# ECUEXT1_23.net
KiCad netlist of a schematic drawn in Altium Designer
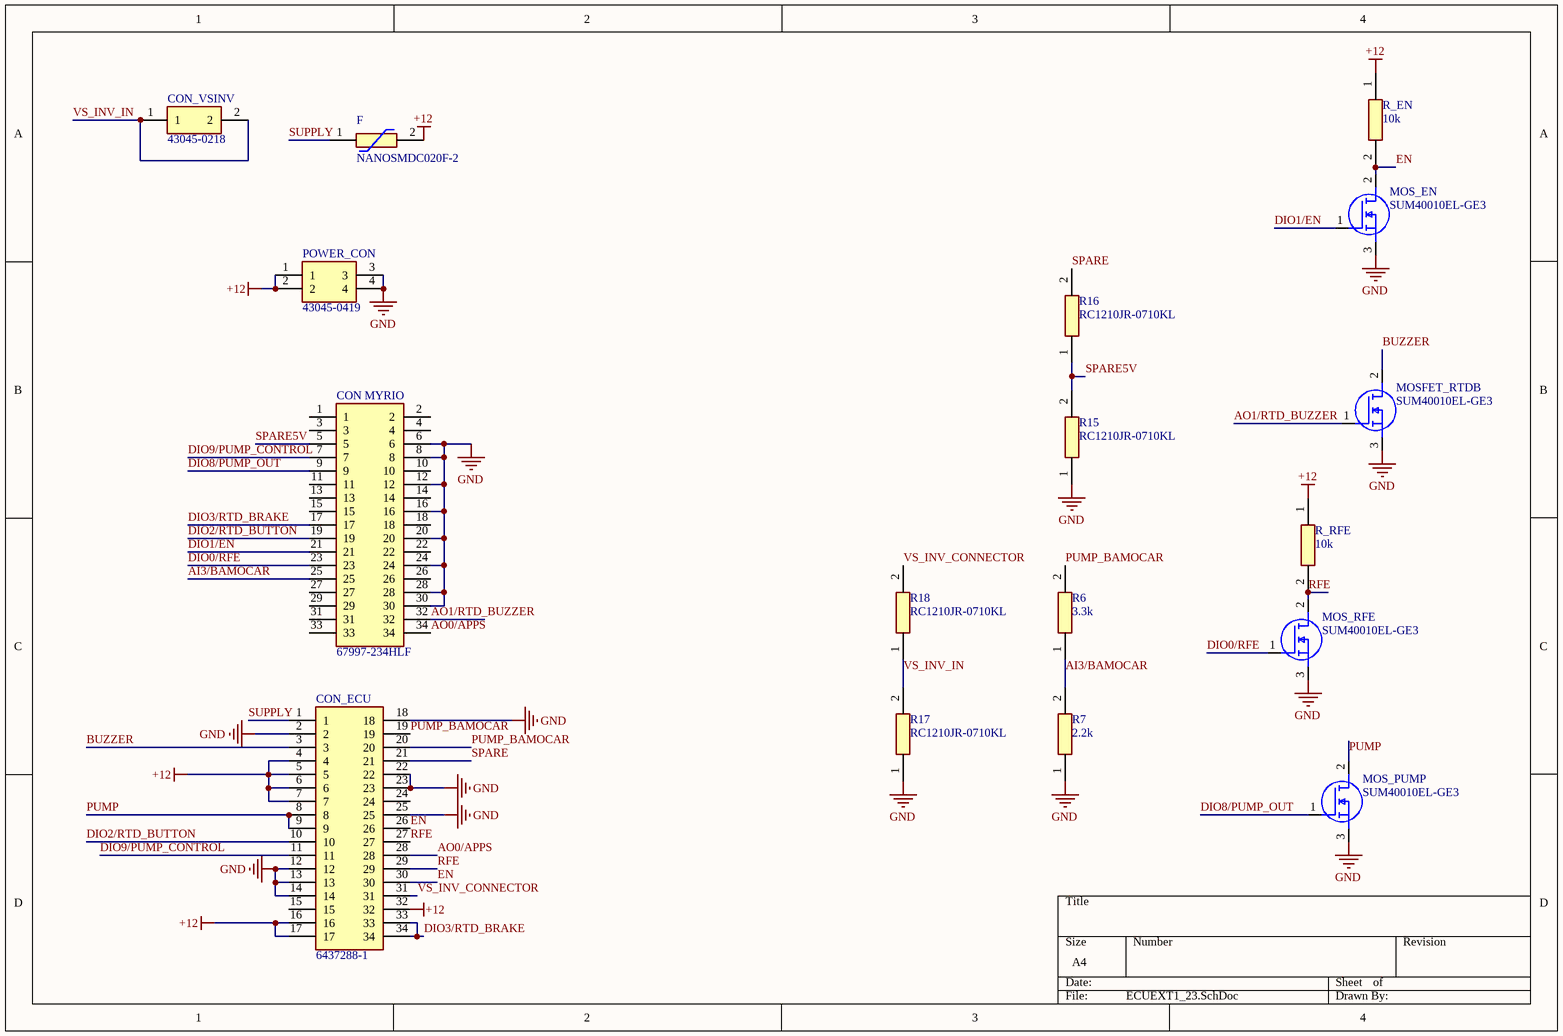
[diagram p0: ECUEXT1_23.SchDoc]

(export (version "E")
  (design (tool "Eeschema 10.0.6"))
  (components
    (comp (ref "CON MYRIO")
      (value "67997-234HLF")
      (footprint "SamacSys:HDRV34W67P254_2X17_4318X483X858P")
      (description "Connector")
      (fields (field (name "MOUSER PART NUMBER") "649-67997-234HLF"))
      (libsource (lib "*") (part "67997-234HLF"))
    )
    (comp (ref "CON_ECU")
      (value "6437288-1")
      (footprint "SamacSys:6437288-1")
      (description "Connector")
      (fields (field (name "MOUSER PART NUMBER") "571-6437288-1"))
      (libsource (lib "SamacSys") (part "6437288-1"))
    )
    (comp (ref "CON_VSINV")
      (value "43045-0218")
      (footprint "SamacSys:43045-02YY_181920")
      (description "Connector")
      (fields (field (name "MOUSER PART NUMBER") "538-43045-0218"))
      (libsource (lib "SamacSys") (part "43045-0218"))
    )
    (comp (ref "F")
      (value "NANOSMDC020F-2")
      (footprint "SamacSys:NANOSMDC016F2")
      (description "Resettable Fuse")
      (fields (field (name "MOUSER PART NUMBER") "650-NANOSMDC020F-2"))
      (libsource (lib "*") (part "NANOSMDC020F-2"))
    )
    (comp (ref "MOSFET_RTDB")
      (value "SUM40010EL-GE3")
      (footprint "SamacSys:SUM40010ELGE3")
      (description "MOSFET (N-Channel)")
      (fields (field (name "MOUSER PART NUMBER") "78-SUM40010EL-GE3"))
      (libsource (lib "SamacSys") (part "SUM40010EL-GE3"))
    )
    (comp (ref "MOS_EN")
      (value "SUM40010EL-GE3")
      (footprint "SamacSys:SUM40010ELGE3")
      (description "MOSFET (N-Channel)")
      (fields (field (name "MOUSER PART NUMBER") "78-SUM40010EL-GE3"))
      (libsource (lib "SamacSys") (part "SUM40010EL-GE3"))
    )
    (comp (ref "MOS_PUMP")
      (value "SUM40010EL-GE3")
      (footprint "SamacSys:SUM40010ELGE3")
      (description "MOSFET (N-Channel)")
      (fields (field (name "MOUSER PART NUMBER") "78-SUM40010EL-GE3"))
      (libsource (lib "SamacSys") (part "SUM40010EL-GE3"))
    )
    (comp (ref "MOS_RFE")
      (value "SUM40010EL-GE3")
      (footprint "SamacSys:SUM40010ELGE3")
      (description "MOSFET (N-Channel)")
      (fields (field (name "MOUSER PART NUMBER") "78-SUM40010EL-GE3"))
      (libsource (lib "SamacSys") (part "SUM40010EL-GE3"))
    )
    (comp (ref "POWER_CON")
      (value "43045-0419")
      (footprint "SamacSys:43045-04YY_181920")
      (description "Connector")
      (fields (field (name "MOUSER PART NUMBER") "538-43045-0419"))
      (libsource (lib "SamacSys") (part "43045-0419"))
    )
    (comp (ref "R6")
      (value "3.3k")
      (footprint "SamacSys:RESC3126X60N")
      (description "Resistor")
      (fields
        (field (name "MANUFACTURER_PART_NUMBER") "RC1210JR-0710KL")
        (field (name "MOUSER PART NUMBER") "603-RC1210JR-0710KL")
      )
      (libsource (lib "*") (part "RC1210JR-0710KL"))
    )
    (comp (ref "R7")
      (value "2.2k")
      (footprint "SamacSys:RESC3126X60N")
      (description "Resistor")
      (fields
        (field (name "MANUFACTURER_PART_NUMBER") "RC1210JR-0710KL")
        (field (name "MOUSER PART NUMBER") "603-RC1210JR-0710KL")
      )
      (libsource (lib "*") (part "RC1210JR-0710KL"))
    )
    (comp (ref "R15")
      (value "RC1210JR-0710KL")
      (footprint "SamacSys:RESC3126X60N")
      (description "Resistor")
      (fields (field (name "MOUSER PART NUMBER") "603-RC1210JR-0710KL"))
      (libsource (lib "SamacSys") (part "RC1210JR-0710KL"))
    )
    (comp (ref "R16")
      (value "RC1210JR-0710KL")
      (footprint "SamacSys:RESC3126X60N")
      (description "Resistor")
      (fields (field (name "MOUSER PART NUMBER") "603-RC1210JR-0710KL"))
      (libsource (lib "SamacSys") (part "RC1210JR-0710KL"))
    )
    (comp (ref "R17")
      (value "RC1210JR-0710KL")
      (footprint "SamacSys:RESC3126X60N")
      (description "Resistor")
      (fields (field (name "MOUSER PART NUMBER") "603-RC1210JR-0710KL"))
      (libsource (lib "SamacSys") (part "RC1210JR-0710KL"))
    )
    (comp (ref "R18")
      (value "RC1210JR-0710KL")
      (footprint "SamacSys:RESC3126X60N")
      (description "Resistor")
      (fields (field (name "MOUSER PART NUMBER") "603-RC1210JR-0710KL"))
      (libsource (lib "SamacSys") (part "RC1210JR-0710KL"))
    )
    (comp (ref "R_EN")
      (value "10k")
      (footprint "SamacSys:RESC3126X60N")
      (description "Resistor")
      (fields
        (field (name "MANUFACTURER_PART_NUMBER") "RC1210JR-0710KL")
        (field (name "MOUSER PART NUMBER") "603-RC1210JR-0710KL")
      )
      (libsource (lib "") (part "RC1210JR-0710KL_1"))
    )
    (comp (ref "R_RFE")
      (value "10k")
      (footprint "SamacSys:RESC3126X60N")
      (description "Resistor")
      (fields
        (field (name "MANUFACTURER_PART_NUMBER") "RC1210JR-0710KL")
        (field (name "MOUSER PART NUMBER") "603-RC1210JR-0710KL")
      )
      (libsource (lib "") (part "RC1210JR-0710KL_1"))
    )
  )
  (nets
    (net (code "1") (name "+12") (class "Default")
      (node (ref "CON_ECU") (pin "16") (pinfunction "16_16") (pintype "passive"))
      (node (ref "CON_ECU") (pin "17") (pinfunction "17_17") (pintype "passive"))
      (node (ref "CON_ECU") (pin "32") (pinfunction "32_32") (pintype "passive"))
      (node (ref "CON_ECU") (pin "4") (pinfunction "4_4") (pintype "passive"))
      (node (ref "CON_ECU") (pin "5") (pinfunction "5_5") (pintype "passive"))
      (node (ref "CON_ECU") (pin "6") (pinfunction "6_6") (pintype "passive"))
      (node (ref "CON_ECU") (pin "7") (pinfunction "7_7") (pintype "passive"))
      (node (ref "F") (pin "2") (pinfunction "2_2") (pintype "passive"))
      (node (ref "POWER_CON") (pin "1") (pinfunction "1_1") (pintype "passive"))
      (node (ref "POWER_CON") (pin "2") (pinfunction "2_2") (pintype "passive"))
      (node (ref "R_EN") (pin "1") (pinfunction "1_1") (pintype "passive"))
      (node (ref "R_RFE") (pin "1") (pinfunction "1_1") (pintype "passive"))
    )
    (net (code "2") (name "/AI3{slash}BAMOCAR") (class "Default")
      (node (ref "CON MYRIO") (pin "25") (pinfunction "25_25") (pintype "passive"))
      (node (ref "R6") (pin "1") (pinfunction "1_1") (pintype "passive"))
      (node (ref "R7") (pin "2") (pinfunction "2_2") (pintype "passive"))
    )
    (net (code "3") (name "/AO0{slash}APPS") (class "Default")
      (node (ref "CON MYRIO") (pin "34") (pinfunction "34_34") (pintype "passive"))
      (node (ref "CON_ECU") (pin "28") (pinfunction "28_28") (pintype "passive"))
    )
    (net (code "4") (name "/AO1{slash}RTD_BUZZER") (class "Default")
      (node (ref "CON MYRIO") (pin "32") (pinfunction "32_32") (pintype "passive"))
      (node (ref "MOSFET_RTDB") (pin "1") (pinfunction "G_1") (pintype "passive"))
    )
    (net (code "5") (name "/BUZZER") (class "Default")
      (node (ref "CON_ECU") (pin "3") (pinfunction "3_3") (pintype "passive"))
      (node (ref "MOSFET_RTDB") (pin "2") (pinfunction "D_2") (pintype "passive"))
    )
    (net (code "6") (name "/DIO0{slash}RFE") (class "Default")
      (node (ref "CON MYRIO") (pin "23") (pinfunction "23_23") (pintype "passive"))
      (node (ref "MOS_RFE") (pin "1") (pinfunction "G_1") (pintype "passive"))
    )
    (net (code "7") (name "/DIO1{slash}EN") (class "Default")
      (node (ref "CON MYRIO") (pin "21") (pinfunction "21_21") (pintype "passive"))
      (node (ref "MOS_EN") (pin "1") (pinfunction "G_1") (pintype "passive"))
    )
    (net (code "8") (name "/DIO2{slash}RTD_BUTTON") (class "Default")
      (node (ref "CON MYRIO") (pin "19") (pinfunction "19_19") (pintype "passive"))
      (node (ref "CON_ECU") (pin "10") (pinfunction "10_10") (pintype "passive"))
    )
    (net (code "9") (name "/DIO3{slash}RTD_BRAKE") (class "Default")
      (node (ref "CON MYRIO") (pin "17") (pinfunction "17_17") (pintype "passive"))
      (node (ref "CON_ECU") (pin "33") (pinfunction "33_33") (pintype "passive"))
      (node (ref "CON_ECU") (pin "34") (pinfunction "34_34") (pintype "passive"))
    )
    (net (code "10") (name "/DIO8{slash}PUMP_OUT") (class "Default")
      (node (ref "CON MYRIO") (pin "9") (pinfunction "9_9") (pintype "passive"))
      (node (ref "MOS_PUMP") (pin "1") (pinfunction "G_1") (pintype "passive"))
    )
    (net (code "11") (name "/DIO9{slash}PUMP_CONTROL") (class "Default")
      (node (ref "CON MYRIO") (pin "7") (pinfunction "7_7") (pintype "passive"))
      (node (ref "CON_ECU") (pin "11") (pinfunction "11_11") (pintype "passive"))
    )
    (net (code "12") (name "/EN") (class "Default")
      (node (ref "CON_ECU") (pin "26") (pinfunction "26_26") (pintype "passive"))
      (node (ref "CON_ECU") (pin "30") (pinfunction "30_30") (pintype "passive"))
      (node (ref "MOS_EN") (pin "2") (pinfunction "D_2") (pintype "passive"))
      (node (ref "R_EN") (pin "2") (pinfunction "2_2") (pintype "passive"))
    )
    (net (code "13") (name "/PUMP") (class "Default")
      (node (ref "CON_ECU") (pin "8") (pinfunction "8_8") (pintype "passive"))
      (node (ref "CON_ECU") (pin "9") (pinfunction "9_9") (pintype "passive"))
      (node (ref "MOS_PUMP") (pin "2") (pinfunction "D_2") (pintype "passive"))
    )
    (net (code "14") (name "/PUMP_BAMOCAR") (class "Default")
      (node (ref "CON_ECU") (pin "19") (pinfunction "19_19") (pintype "passive"))
      (node (ref "CON_ECU") (pin "20") (pinfunction "20_20") (pintype "passive"))
      (node (ref "R6") (pin "2") (pinfunction "2_2") (pintype "passive"))
    )
    (net (code "15") (name "/RFE") (class "Default")
      (node (ref "CON_ECU") (pin "27") (pinfunction "27_27") (pintype "passive"))
      (node (ref "CON_ECU") (pin "29") (pinfunction "29_29") (pintype "passive"))
      (node (ref "MOS_RFE") (pin "2") (pinfunction "D_2") (pintype "passive"))
      (node (ref "R_RFE") (pin "2") (pinfunction "2_2") (pintype "passive"))
    )
    (net (code "16") (name "/SPARE") (class "Default")
      (node (ref "CON_ECU") (pin "21") (pinfunction "21_21") (pintype "passive"))
      (node (ref "R16") (pin "2") (pinfunction "2_2") (pintype "passive"))
    )
    (net (code "17") (name "/SPARE5V") (class "Default")
      (node (ref "CON MYRIO") (pin "5") (pinfunction "5_5") (pintype "passive"))
      (node (ref "R15") (pin "2") (pinfunction "2_2") (pintype "passive"))
      (node (ref "R16") (pin "1") (pinfunction "1_1") (pintype "passive"))
    )
    (net (code "18") (name "/SUPPLY") (class "Default")
      (node (ref "CON_ECU") (pin "1") (pinfunction "1_1") (pintype "passive"))
      (node (ref "F") (pin "1") (pinfunction "1_1") (pintype "passive"))
    )
    (net (code "19") (name "/VS_INV_CONNECTOR") (class "Default")
      (node (ref "CON_ECU") (pin "31") (pinfunction "31_31") (pintype "passive"))
      (node (ref "R18") (pin "2") (pinfunction "2_2") (pintype "passive"))
    )
    (net (code "20") (name "/VS_INV_IN") (class "Default")
      (node (ref "CON_VSINV") (pin "1") (pinfunction "1_1") (pintype "passive"))
      (node (ref "CON_VSINV") (pin "2") (pinfunction "2_2") (pintype "passive"))
      (node (ref "R17") (pin "2") (pinfunction "2_2") (pintype "passive"))
      (node (ref "R18") (pin "1") (pinfunction "1_1") (pintype "passive"))
    )
    (net (code "21") (name "GND") (class "Default")
      (node (ref "CON MYRIO") (pin "12") (pinfunction "12_12") (pintype "passive"))
      (node (ref "CON MYRIO") (pin "16") (pinfunction "16_16") (pintype "passive"))
      (node (ref "CON MYRIO") (pin "20") (pinfunction "20_20") (pintype "passive"))
      (node (ref "CON MYRIO") (pin "24") (pinfunction "24_24") (pintype "passive"))
      (node (ref "CON MYRIO") (pin "28") (pinfunction "28_28") (pintype "passive"))
      (node (ref "CON MYRIO") (pin "30") (pinfunction "30_30") (pintype "passive"))
      (node (ref "CON MYRIO") (pin "6") (pinfunction "6_6") (pintype "passive"))
      (node (ref "CON MYRIO") (pin "8") (pinfunction "8_8") (pintype "passive"))
      (node (ref "CON_ECU") (pin "12") (pinfunction "12_12") (pintype "passive"))
      (node (ref "CON_ECU") (pin "13") (pinfunction "13_13") (pintype "passive"))
      (node (ref "CON_ECU") (pin "14") (pinfunction "14_14") (pintype "passive"))
      (node (ref "CON_ECU") (pin "18") (pinfunction "18_18") (pintype "passive"))
      (node (ref "CON_ECU") (pin "2") (pinfunction "2_2") (pintype "passive"))
      (node (ref "CON_ECU") (pin "22") (pinfunction "22_22") (pintype "passive"))
      (node (ref "CON_ECU") (pin "23") (pinfunction "23_23") (pintype "passive"))
      (node (ref "CON_ECU") (pin "25") (pinfunction "25_25") (pintype "passive"))
      (node (ref "MOSFET_RTDB") (pin "3") (pinfunction "S_3") (pintype "passive"))
      (node (ref "MOS_EN") (pin "3") (pinfunction "S_3") (pintype "passive"))
      (node (ref "MOS_PUMP") (pin "3") (pinfunction "S_3") (pintype "passive"))
      (node (ref "MOS_RFE") (pin "3") (pinfunction "S_3") (pintype "passive"))
      (node (ref "POWER_CON") (pin "3") (pinfunction "3_3") (pintype "passive"))
      (node (ref "POWER_CON") (pin "4") (pinfunction "4_4") (pintype "passive"))
      (node (ref "R15") (pin "1") (pinfunction "1_1") (pintype "passive"))
      (node (ref "R17") (pin "1") (pinfunction "1_1") (pintype "passive"))
      (node (ref "R7") (pin "1") (pinfunction "1_1") (pintype "passive"))
    )
    (net (code "22") (name "unconnected-(CON MYRIO-Pad1)") (class "Default")
      (node (ref "CON MYRIO") (pin "1") (pinfunction "1_1") (pintype "passive"))
    )
    (net (code "23") (name "unconnected-(CON MYRIO-Pad2)") (class "Default")
      (node (ref "CON MYRIO") (pin "2") (pinfunction "2_2") (pintype "passive"))
    )
    (net (code "24") (name "unconnected-(CON MYRIO-Pad3)") (class "Default")
      (node (ref "CON MYRIO") (pin "3") (pinfunction "3_3") (pintype "passive"))
    )
    (net (code "25") (name "unconnected-(CON MYRIO-Pad4)") (class "Default")
      (node (ref "CON MYRIO") (pin "4") (pinfunction "4_4") (pintype "passive"))
    )
    (net (code "26") (name "unconnected-(CON MYRIO-Pad10)") (class "Default")
      (node (ref "CON MYRIO") (pin "10") (pinfunction "10_10") (pintype "passive"))
    )
    (net (code "27") (name "unconnected-(CON MYRIO-Pad11)") (class "Default")
      (node (ref "CON MYRIO") (pin "11") (pinfunction "11_11") (pintype "passive"))
    )
    (net (code "28") (name "unconnected-(CON MYRIO-Pad13)") (class "Default")
      (node (ref "CON MYRIO") (pin "13") (pinfunction "13_13") (pintype "passive"))
    )
    (net (code "29") (name "unconnected-(CON MYRIO-Pad14)") (class "Default")
      (node (ref "CON MYRIO") (pin "14") (pinfunction "14_14") (pintype "passive"))
    )
    (net (code "30") (name "unconnected-(CON MYRIO-Pad15)") (class "Default")
      (node (ref "CON MYRIO") (pin "15") (pinfunction "15_15") (pintype "passive"))
    )
    (net (code "31") (name "unconnected-(CON MYRIO-Pad18)") (class "Default")
      (node (ref "CON MYRIO") (pin "18") (pinfunction "18_18") (pintype "passive"))
    )
    (net (code "32") (name "unconnected-(CON MYRIO-Pad22)") (class "Default")
      (node (ref "CON MYRIO") (pin "22") (pinfunction "22_22") (pintype "passive"))
    )
    (net (code "33") (name "unconnected-(CON MYRIO-Pad26)") (class "Default")
      (node (ref "CON MYRIO") (pin "26") (pinfunction "26_26") (pintype "passive"))
    )
    (net (code "34") (name "unconnected-(CON MYRIO-Pad27)") (class "Default")
      (node (ref "CON MYRIO") (pin "27") (pinfunction "27_27") (pintype "passive"))
    )
    (net (code "35") (name "unconnected-(CON MYRIO-Pad29)") (class "Default")
      (node (ref "CON MYRIO") (pin "29") (pinfunction "29_29") (pintype "passive"))
    )
    (net (code "36") (name "unconnected-(CON MYRIO-Pad31)") (class "Default")
      (node (ref "CON MYRIO") (pin "31") (pinfunction "31_31") (pintype "passive"))
    )
    (net (code "37") (name "unconnected-(CON MYRIO-Pad33)") (class "Default")
      (node (ref "CON MYRIO") (pin "33") (pinfunction "33_33") (pintype "passive"))
    )
    (net (code "38") (name "unconnected-(CON_ECU-Pad15)") (class "Default")
      (node (ref "CON_ECU") (pin "15") (pinfunction "15_15") (pintype "passive"))
    )
    (net (code "39") (name "unconnected-(CON_ECU-Pad24)") (class "Default")
      (node (ref "CON_ECU") (pin "24") (pinfunction "24_24") (pintype "passive"))
    )
  )
)
